# esp-wroom-02-eval-board.net
KiCad netlist of a schematic drawn in EAGLE
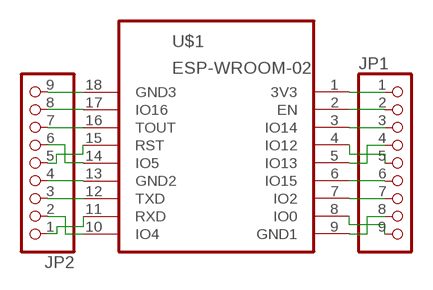
[diagram p0: schematic, sheet 1]

(export (version "E")
  (design (tool "Eeschema 10.0.6"))
  (components
    (comp (ref "JP1")
      (value "PINHD-1X9")
      (footprint "eagle-import:1X09")
      (libsource (lib "eagle-import") (part "PINHD-1X9"))
    )
    (comp (ref "JP2")
      (value "PINHD-1X9")
      (footprint "eagle-import:1X09")
      (libsource (lib "eagle-import") (part "PINHD-1X9"))
    )
    (comp (ref "U$1")
      (value "ESP-WROOM-02")
      (footprint "eagle-import:ESP-WROOM-02")
      (libsource (lib "eagle-import") (part "ESP-WROOM-02"))
    )
  )
  (nets
    (net (code "1") (name "Net-(U$1-3V3)") (class "Default")
      (node (ref "JP1") (pin "1") (pinfunction "1_1") (pintype "passive"))
      (node (ref "U$1") (pin "1") (pinfunction "3V3_1") (pintype "bidirectional"))
    )
    (net (code "2") (name "Net-(U$1-EN)") (class "Default")
      (node (ref "JP1") (pin "2") (pinfunction "2_2") (pintype "passive"))
      (node (ref "U$1") (pin "2") (pinfunction "EN_2") (pintype "bidirectional"))
    )
    (net (code "3") (name "Net-(U$1-GND1)") (class "Default")
      (node (ref "JP1") (pin "8") (pinfunction "8_8") (pintype "passive"))
      (node (ref "U$1") (pin "9") (pinfunction "GND1_9") (pintype "bidirectional"))
    )
    (net (code "4") (name "Net-(U$1-GND2)") (class "Default")
      (node (ref "JP2") (pin "4") (pinfunction "4_4") (pintype "passive"))
      (node (ref "U$1") (pin "13") (pinfunction "GND2_13") (pintype "bidirectional"))
    )
    (net (code "5") (name "Net-(U$1-GND3)") (class "Default")
      (node (ref "JP2") (pin "9") (pinfunction "9_9") (pintype "passive"))
      (node (ref "U$1") (pin "18") (pinfunction "GND3_18") (pintype "bidirectional"))
    )
    (net (code "6") (name "Net-(U$1-IO0)") (class "Default")
      (node (ref "JP1") (pin "9") (pinfunction "9_9") (pintype "passive"))
      (node (ref "U$1") (pin "8") (pinfunction "IO0_8") (pintype "bidirectional"))
    )
    (net (code "7") (name "Net-(U$1-IO2)") (class "Default")
      (node (ref "JP1") (pin "7") (pinfunction "7_7") (pintype "passive"))
      (node (ref "U$1") (pin "7") (pinfunction "IO2_7") (pintype "bidirectional"))
    )
    (net (code "8") (name "Net-(U$1-IO4)") (class "Default")
      (node (ref "JP2") (pin "2") (pinfunction "2_2") (pintype "passive"))
      (node (ref "U$1") (pin "10") (pinfunction "IO4_10") (pintype "bidirectional"))
    )
    (net (code "9") (name "Net-(U$1-IO5)") (class "Default")
      (node (ref "JP2") (pin "6") (pinfunction "6_6") (pintype "passive"))
      (node (ref "U$1") (pin "14") (pinfunction "IO5_14") (pintype "power_in"))
    )
    (net (code "10") (name "Net-(U$1-IO12)") (class "Default")
      (node (ref "JP1") (pin "5") (pinfunction "5_5") (pintype "passive"))
      (node (ref "U$1") (pin "4") (pinfunction "IO12_4") (pintype "power_in"))
    )
    (net (code "11") (name "Net-(U$1-IO13)") (class "Default")
      (node (ref "JP1") (pin "4") (pinfunction "4_4") (pintype "passive"))
      (node (ref "U$1") (pin "5") (pinfunction "IO13_5") (pintype "power_in"))
    )
    (net (code "12") (name "Net-(U$1-IO14)") (class "Default")
      (node (ref "JP1") (pin "3") (pinfunction "3_3") (pintype "passive"))
      (node (ref "U$1") (pin "3") (pinfunction "IO14_3") (pintype "bidirectional"))
    )
    (net (code "13") (name "Net-(U$1-IO15)") (class "Default")
      (node (ref "JP1") (pin "6") (pinfunction "6_6") (pintype "passive"))
      (node (ref "U$1") (pin "6") (pinfunction "IO15_6") (pintype "bidirectional"))
    )
    (net (code "14") (name "Net-(U$1-IO16)") (class "Default")
      (node (ref "JP2") (pin "8") (pinfunction "8_8") (pintype "passive"))
      (node (ref "U$1") (pin "17") (pinfunction "IO16_17") (pintype "bidirectional"))
    )
    (net (code "15") (name "Net-(U$1-RST)") (class "Default")
      (node (ref "JP2") (pin "5") (pinfunction "5_5") (pintype "passive"))
      (node (ref "U$1") (pin "15") (pinfunction "RST_15") (pintype "bidirectional"))
    )
    (net (code "16") (name "Net-(U$1-RXD)") (class "Default")
      (node (ref "JP2") (pin "1") (pinfunction "1_1") (pintype "passive"))
      (node (ref "U$1") (pin "11") (pinfunction "RXD_11") (pintype "bidirectional"))
    )
    (net (code "17") (name "Net-(U$1-TOUT)") (class "Default")
      (node (ref "JP2") (pin "7") (pinfunction "7_7") (pintype "passive"))
      (node (ref "U$1") (pin "16") (pinfunction "TOUT_16") (pintype "bidirectional"))
    )
    (net (code "18") (name "Net-(U$1-TXD)") (class "Default")
      (node (ref "JP2") (pin "3") (pinfunction "3_3") (pintype "passive"))
      (node (ref "U$1") (pin "12") (pinfunction "TXD_12") (pintype "bidirectional"))
    )
  )
)
